# ft2232h-breakout-with-ground-planesch.net
KiCad netlist of a schematic drawn in EAGLE
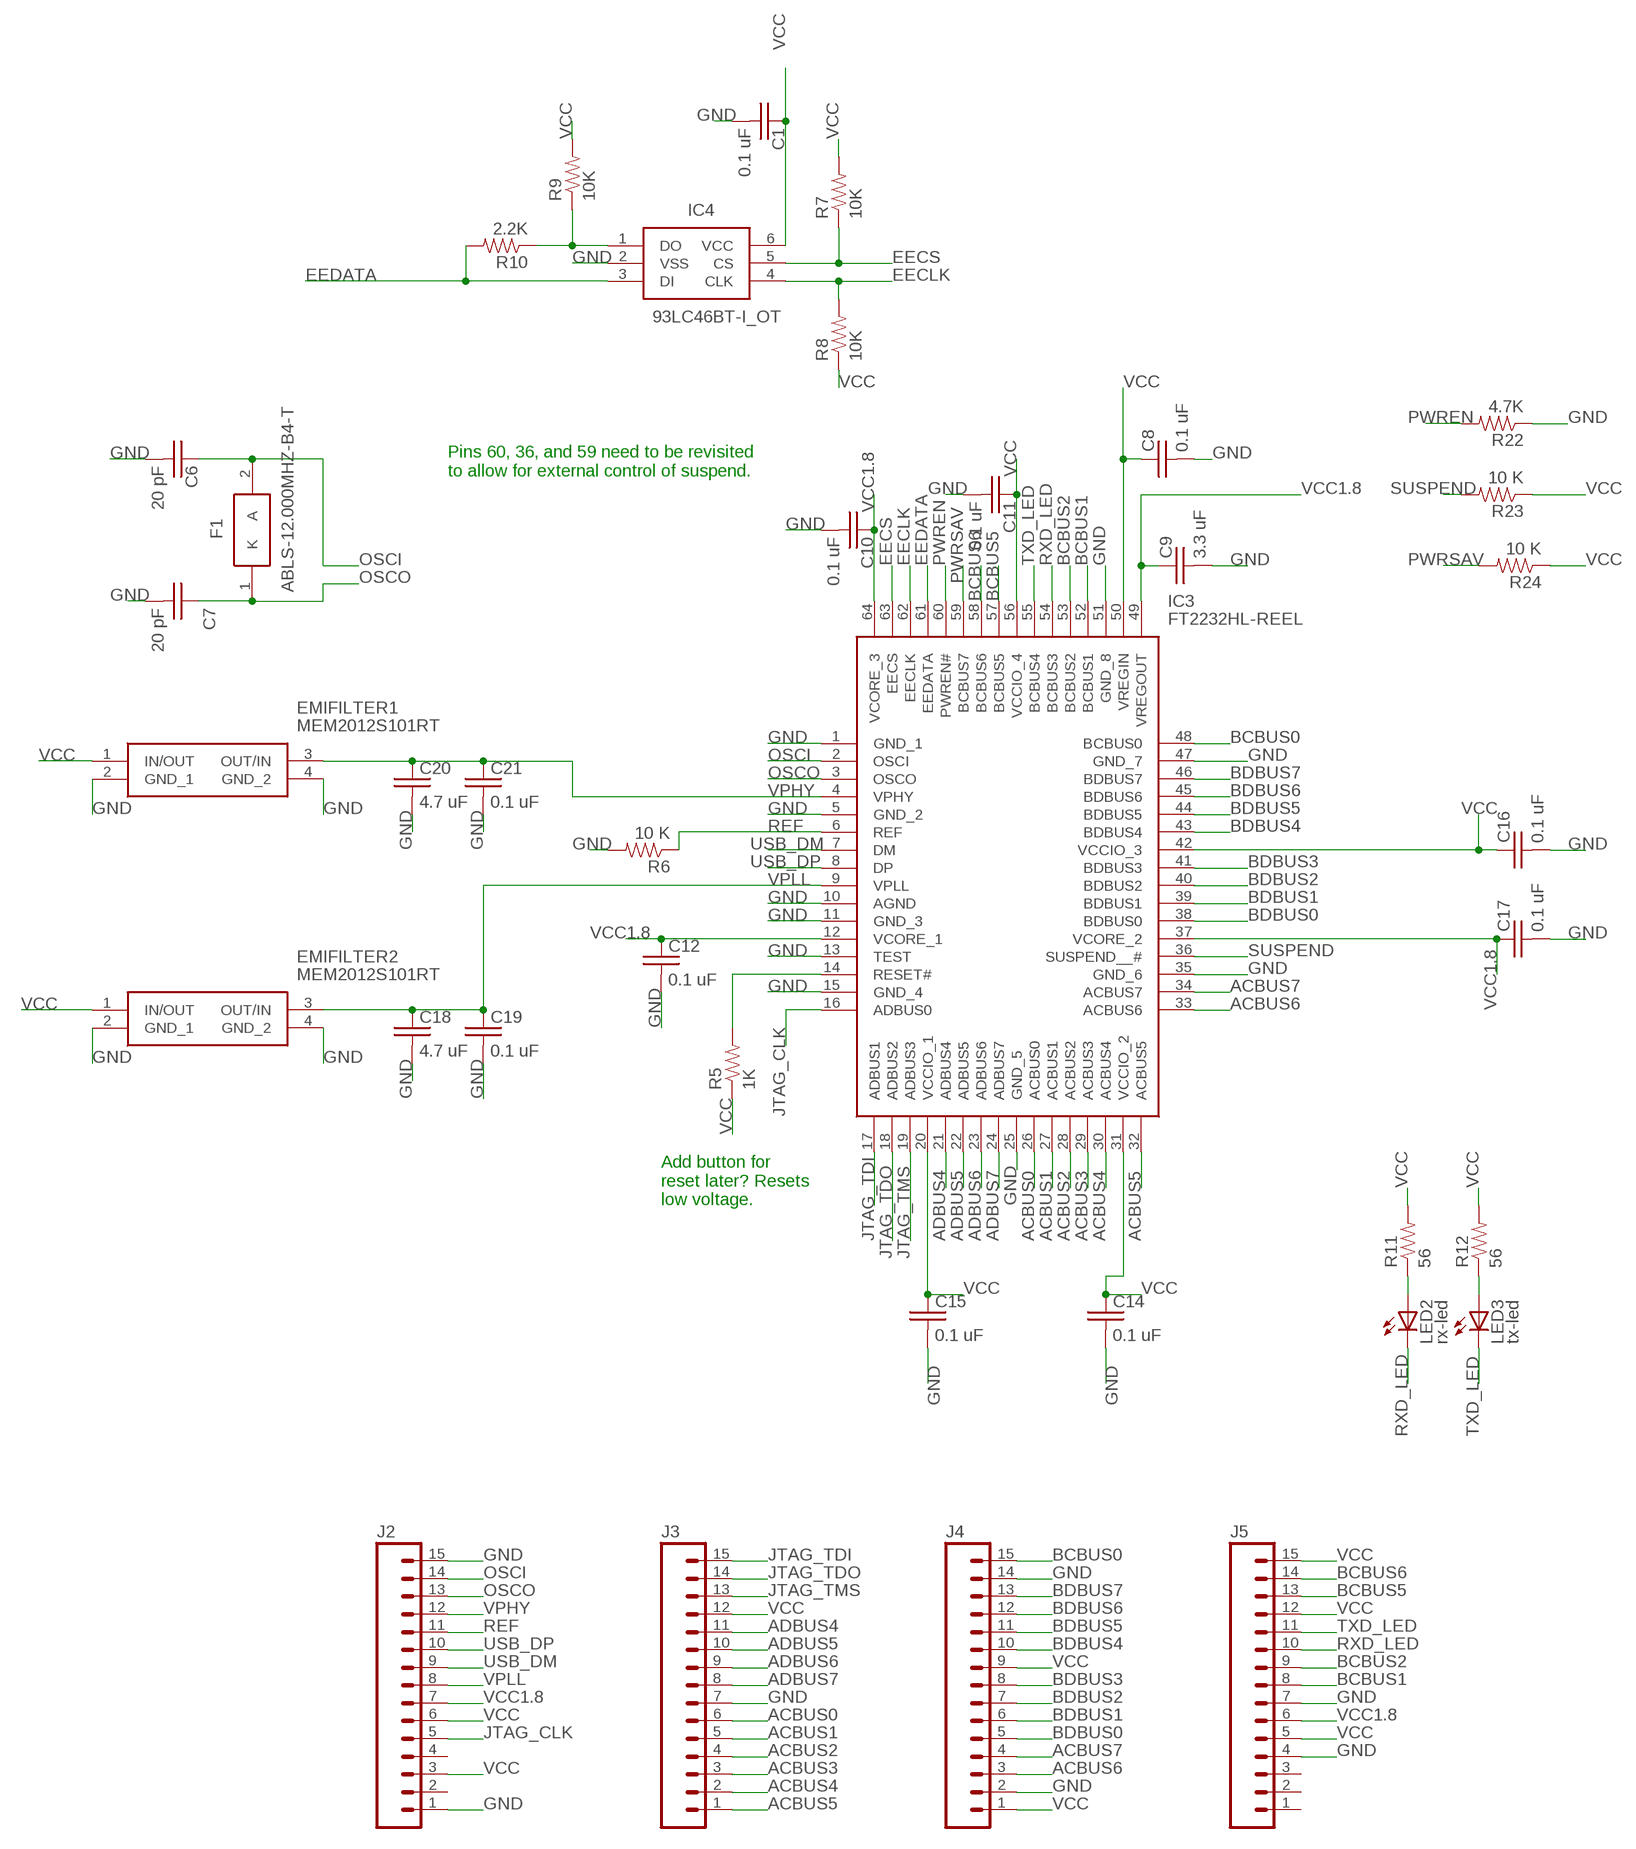
[diagram p0: schematic, sheet 1]
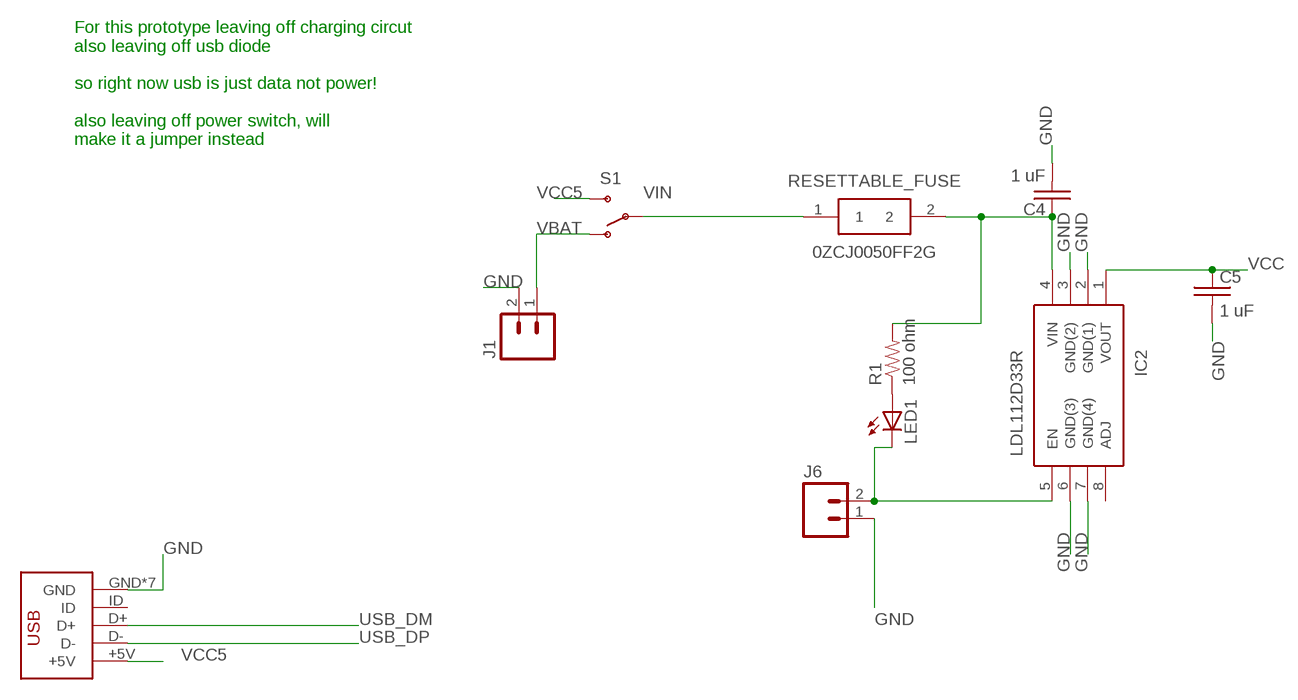
[diagram p1: schematic, sheet 2]

(export (version "E")
  (design (tool "Eeschema 10.0.6"))
  (components
    (comp (ref "C1")
      (value "0.1 uF")
      (footprint "eagle-import:C0805")
      (libsource (lib "eagle-import") (part "C-USC0805"))
    )
    (comp (ref "C6")
      (value "20 pF")
      (footprint "eagle-import:C0805")
      (libsource (lib "eagle-import") (part "C-USC0805"))
    )
    (comp (ref "C7")
      (value "20 pF")
      (footprint "eagle-import:C0805")
      (libsource (lib "eagle-import") (part "C-USC0805"))
    )
    (comp (ref "C8")
      (value "0.1 uF")
      (footprint "eagle-import:C0805")
      (libsource (lib "eagle-import") (part "C-USC0805"))
    )
    (comp (ref "C9")
      (value "3.3 uF")
      (footprint "eagle-import:C0805")
      (libsource (lib "eagle-import") (part "C-USC0805"))
    )
    (comp (ref "C10")
      (value "0.1 uF")
      (footprint "eagle-import:C0805")
      (libsource (lib "eagle-import") (part "C-USC0805"))
    )
    (comp (ref "C11")
      (value "0.1 uF")
      (footprint "eagle-import:C0805")
      (libsource (lib "eagle-import") (part "C-USC0805"))
    )
    (comp (ref "C12")
      (value "0.1 uF")
      (footprint "eagle-import:C0805")
      (libsource (lib "eagle-import") (part "C-USC0805"))
    )
    (comp (ref "C14")
      (value "0.1 uF")
      (footprint "eagle-import:C0805")
      (libsource (lib "eagle-import") (part "C-USC0805"))
    )
    (comp (ref "C15")
      (value "0.1 uF")
      (footprint "eagle-import:C0805")
      (libsource (lib "eagle-import") (part "C-USC0805"))
    )
    (comp (ref "C16")
      (value "0.1 uF")
      (footprint "eagle-import:C0805")
      (libsource (lib "eagle-import") (part "C-USC0805"))
    )
    (comp (ref "C17")
      (value "0.1 uF")
      (footprint "eagle-import:C0805")
      (libsource (lib "eagle-import") (part "C-USC0805"))
    )
    (comp (ref "C18")
      (value "4.7 uF")
      (footprint "eagle-import:C0805")
      (libsource (lib "eagle-import") (part "C-USC0805"))
    )
    (comp (ref "C19")
      (value "0.1 uF")
      (footprint "eagle-import:C0805")
      (libsource (lib "eagle-import") (part "C-USC0805"))
    )
    (comp (ref "C20")
      (value "4.7 uF")
      (footprint "eagle-import:C0805")
      (libsource (lib "eagle-import") (part "C-USC0805"))
    )
    (comp (ref "C21")
      (value "0.1 uF")
      (footprint "eagle-import:C0805")
      (libsource (lib "eagle-import") (part "C-USC0805"))
    )
    (comp (ref "EMIFILTER1")
      (value "MEM2012S101RT")
      (footprint "eagle-import:MEM2012S101RT")
      (libsource (lib "eagle-import") (part "MEM2012S101RT"))
    )
    (comp (ref "EMIFILTER2")
      (value "MEM2012S101RT")
      (footprint "eagle-import:MEM2012S101RT")
      (libsource (lib "eagle-import") (part "MEM2012S101RT"))
    )
    (comp (ref "F1")
      (value "ABLS-12.000MHZ-B4-T")
      (footprint "eagle-import:HC_49US-(AT49)_1")
      (fields
        (field (name "MOUSER_PART_NUMBER") "815-ABLS-12.0M-T")
        (field (name "RS_PART_NUMBER") "1710207")
      )
      (libsource (lib "eagle-import") (part "ABLS-12.000MHZ-B4-T"))
    )
    (comp (ref "IC3")
      (value "FT2232HL-REEL")
      (footprint "eagle-import:QFP50P1200X1200X160-64N")
      (fields (field (name "MOUSER_PART_NUMBER") "895-FT2232HL"))
      (libsource (lib "eagle-import") (part "FT2232HL-REEL"))
    )
    (comp (ref "IC4")
      (value "93LC46BT-I_OT")
      (footprint "eagle-import:SOT95P270X145-6N")
      (fields
        (field (name "MANUFACTURER_PART_NUMBER") "93LC46BT-I/OT")
        (field (name "MOUSER_PART_NUMBER") "579-93LC46BT-I/OT")
      )
      (libsource (lib "eagle-import") (part "93LC46BT-I_OT"))
    )
    (comp (ref "J2")
      (value "M15")
      (footprint "eagle-import:1X15")
      (libsource (lib "eagle-import") (part "M15"))
    )
    (comp (ref "J3")
      (value "M15")
      (footprint "eagle-import:1X15")
      (libsource (lib "eagle-import") (part "M15"))
    )
    (comp (ref "J4")
      (value "M15")
      (footprint "eagle-import:1X15")
      (libsource (lib "eagle-import") (part "M15"))
    )
    (comp (ref "J5")
      (value "M15")
      (footprint "eagle-import:1X15")
      (libsource (lib "eagle-import") (part "M15"))
    )
    (comp (ref "LED2")
      (value "rx-led")
      (footprint "eagle-import:LED3MM")
      (libsource (lib "eagle-import") (part "LED3MM"))
    )
    (comp (ref "LED3")
      (value "tx-led")
      (footprint "eagle-import:LED3MM")
      (libsource (lib "eagle-import") (part "LED3MM"))
    )
    (comp (ref "R5")
      (value "1K")
      (footprint "eagle-import:0805")
      (libsource (lib "eagle-import") (part "RESISTOR0805-RES"))
    )
    (comp (ref "R6")
      (value "10 K")
      (footprint "eagle-import:0805")
      (libsource (lib "eagle-import") (part "RESISTOR0805-RES"))
    )
    (comp (ref "R7")
      (value "10K")
      (footprint "eagle-import:0805")
      (libsource (lib "eagle-import") (part "RESISTOR0805-RES"))
    )
    (comp (ref "R8")
      (value "10K")
      (footprint "eagle-import:0805")
      (libsource (lib "eagle-import") (part "RESISTOR0805-RES"))
    )
    (comp (ref "R9")
      (value "10K")
      (footprint "eagle-import:0805")
      (libsource (lib "eagle-import") (part "RESISTOR0805-RES"))
    )
    (comp (ref "R10")
      (value "2.2K")
      (footprint "eagle-import:0805")
      (libsource (lib "eagle-import") (part "RESISTOR0805-RES"))
    )
    (comp (ref "R11")
      (value "56")
      (footprint "eagle-import:0805")
      (libsource (lib "eagle-import") (part "RESISTOR0805-RES"))
    )
    (comp (ref "R12")
      (value "56")
      (footprint "eagle-import:0805")
      (libsource (lib "eagle-import") (part "RESISTOR0805-RES"))
    )
    (comp (ref "R22")
      (value "4.7K")
      (footprint "eagle-import:0805")
      (libsource (lib "eagle-import") (part "RESISTOR0805-RES"))
    )
    (comp (ref "R23")
      (value "10 K")
      (footprint "eagle-import:0805")
      (libsource (lib "eagle-import") (part "RESISTOR0805-RES"))
    )
    (comp (ref "R24")
      (value "10 K")
      (footprint "eagle-import:0805")
      (libsource (lib "eagle-import") (part "RESISTOR0805-RES"))
    )
    (comp (ref "C4")
      (value "1 uF")
      (footprint "eagle-import:C0805")
      (libsource (lib "eagle-import") (part "C-USC0805"))
    )
    (comp (ref "C5")
      (value "1 uF")
      (footprint "eagle-import:C0805")
      (libsource (lib "eagle-import") (part "C-USC0805"))
    )
    (comp (ref "IC2")
      (value "LDL112D33R")
      (footprint "eagle-import:SOIC127P600X175-8N")
      (libsource (lib "eagle-import") (part "LDL112D33R"))
    )
    (comp (ref "J1")
      (value "M02PTH")
      (footprint "eagle-import:1X02")
      (libsource (lib "eagle-import") (part "M02PTH"))
    )
    (comp (ref "J6")
      (value "M02PTH")
      (footprint "eagle-import:1X02")
      (libsource (lib "eagle-import") (part "M02PTH"))
    )
    (comp (ref "LED1")
      (value "LED3MM")
      (footprint "eagle-import:LED3MM")
      (libsource (lib "eagle-import") (part "LED3MM"))
    )
    (comp (ref "R1")
      (value "100 ohm")
      (footprint "eagle-import:AXIAL-0.3-KIT")
      (libsource (lib "eagle-import") (part "RESISTORKIT"))
    )
    (comp (ref "RESETTABLE_FUSE")
      (value "0ZCJ0050FF2G")
      (footprint "eagle-import:FUSC3216X55N")
      (libsource (lib "eagle-import") (part "0ZCJ0050FF2G"))
    )
    (comp (ref "S1")
      (value "SWITCH-SPSTPTH")
      (footprint "eagle-import:SWITCH-SPDT")
      (libsource (lib "eagle-import") (part "SWITCH-SPSTPTH"))
    )
    (comp (ref "U$2")
      (value "DX4R005JJ2DX4R005JJ2")
      (footprint "eagle-import:DX4R005JJ2")
      (libsource (lib "eagle-import") (part "DX4R005JJ2DX4R005JJ2"))
    )
  )
  (nets
    (net (code "1") (name "ACBUS0") (class "Default")
      (node (ref "IC3") (pin "26") (pinfunction "ACBUS0_26") (pintype "bidirectional"))
      (node (ref "J3") (pin "6") (pinfunction "6_6") (pintype "passive"))
    )
    (net (code "2") (name "ACBUS1") (class "Default")
      (node (ref "IC3") (pin "27") (pinfunction "ACBUS1_27") (pintype "bidirectional"))
      (node (ref "J3") (pin "5") (pinfunction "5_5") (pintype "passive"))
    )
    (net (code "3") (name "ACBUS2") (class "Default")
      (node (ref "IC3") (pin "28") (pinfunction "ACBUS2_28") (pintype "bidirectional"))
      (node (ref "J3") (pin "4") (pinfunction "4_4") (pintype "passive"))
    )
    (net (code "4") (name "ACBUS3") (class "Default")
      (node (ref "IC3") (pin "29") (pinfunction "ACBUS3_29") (pintype "bidirectional"))
      (node (ref "J3") (pin "3") (pinfunction "3_3") (pintype "passive"))
    )
    (net (code "5") (name "ACBUS4") (class "Default")
      (node (ref "IC3") (pin "30") (pinfunction "ACBUS4_30") (pintype "bidirectional"))
      (node (ref "J3") (pin "2") (pinfunction "2_2") (pintype "passive"))
    )
    (net (code "6") (name "ACBUS5") (class "Default")
      (node (ref "IC3") (pin "32") (pinfunction "ACBUS5_32") (pintype "bidirectional"))
      (node (ref "J3") (pin "1") (pinfunction "1_1") (pintype "passive"))
    )
    (net (code "7") (name "ACBUS6") (class "Default")
      (node (ref "IC3") (pin "33") (pinfunction "ACBUS6_33") (pintype "bidirectional"))
      (node (ref "J4") (pin "3") (pinfunction "3_3") (pintype "passive"))
    )
    (net (code "8") (name "ACBUS7") (class "Default")
      (node (ref "IC3") (pin "34") (pinfunction "ACBUS7_34") (pintype "bidirectional"))
      (node (ref "J4") (pin "4") (pinfunction "4_4") (pintype "passive"))
    )
    (net (code "9") (name "ADBUS4") (class "Default")
      (node (ref "IC3") (pin "21") (pinfunction "ADBUS4_21") (pintype "bidirectional"))
      (node (ref "J3") (pin "11") (pinfunction "11_11") (pintype "passive"))
    )
    (net (code "10") (name "ADBUS5") (class "Default")
      (node (ref "IC3") (pin "22") (pinfunction "ADBUS5_22") (pintype "bidirectional"))
      (node (ref "J3") (pin "10") (pinfunction "10_10") (pintype "passive"))
    )
    (net (code "11") (name "ADBUS6") (class "Default")
      (node (ref "IC3") (pin "23") (pinfunction "ADBUS6_23") (pintype "bidirectional"))
      (node (ref "J3") (pin "9") (pinfunction "9_9") (pintype "passive"))
    )
    (net (code "12") (name "ADBUS7") (class "Default")
      (node (ref "IC3") (pin "24") (pinfunction "ADBUS7_24") (pintype "bidirectional"))
      (node (ref "J3") (pin "8") (pinfunction "8_8") (pintype "passive"))
    )
    (net (code "13") (name "BCBUS0") (class "Default")
      (node (ref "IC3") (pin "48") (pinfunction "BCBUS0_48") (pintype "bidirectional"))
      (node (ref "J4") (pin "15") (pinfunction "15_15") (pintype "passive"))
    )
    (net (code "14") (name "BCBUS1") (class "Default")
      (node (ref "IC3") (pin "52") (pinfunction "BCBUS1_52") (pintype "bidirectional"))
      (node (ref "J5") (pin "8") (pinfunction "8_8") (pintype "passive"))
    )
    (net (code "15") (name "BCBUS2") (class "Default")
      (node (ref "IC3") (pin "53") (pinfunction "BCBUS2_53") (pintype "bidirectional"))
      (node (ref "J5") (pin "9") (pinfunction "9_9") (pintype "passive"))
    )
    (net (code "16") (name "BCBUS5") (class "Default")
      (node (ref "IC3") (pin "57") (pinfunction "BCBUS5_57") (pintype "bidirectional"))
      (node (ref "J5") (pin "13") (pinfunction "13_13") (pintype "passive"))
    )
    (net (code "17") (name "BCBUS6") (class "Default")
      (node (ref "IC3") (pin "58") (pinfunction "BCBUS6_58") (pintype "bidirectional"))
      (node (ref "J5") (pin "14") (pinfunction "14_14") (pintype "passive"))
    )
    (net (code "18") (name "BDBUS0") (class "Default")
      (node (ref "IC3") (pin "38") (pinfunction "BDBUS0_38") (pintype "bidirectional"))
      (node (ref "J4") (pin "5") (pinfunction "5_5") (pintype "passive"))
    )
    (net (code "19") (name "BDBUS1") (class "Default")
      (node (ref "IC3") (pin "39") (pinfunction "BDBUS1_39") (pintype "bidirectional"))
      (node (ref "J4") (pin "6") (pinfunction "6_6") (pintype "passive"))
    )
    (net (code "20") (name "BDBUS2") (class "Default")
      (node (ref "IC3") (pin "40") (pinfunction "BDBUS2_40") (pintype "bidirectional"))
      (node (ref "J4") (pin "7") (pinfunction "7_7") (pintype "passive"))
    )
    (net (code "21") (name "BDBUS3") (class "Default")
      (node (ref "IC3") (pin "41") (pinfunction "BDBUS3_41") (pintype "bidirectional"))
      (node (ref "J4") (pin "8") (pinfunction "8_8") (pintype "passive"))
    )
    (net (code "22") (name "BDBUS4") (class "Default")
      (node (ref "IC3") (pin "43") (pinfunction "BDBUS4_43") (pintype "bidirectional"))
      (node (ref "J4") (pin "10") (pinfunction "10_10") (pintype "passive"))
    )
    (net (code "23") (name "BDBUS5") (class "Default")
      (node (ref "IC3") (pin "44") (pinfunction "BDBUS5_44") (pintype "bidirectional"))
      (node (ref "J4") (pin "11") (pinfunction "11_11") (pintype "passive"))
    )
    (net (code "24") (name "BDBUS6") (class "Default")
      (node (ref "IC3") (pin "45") (pinfunction "BDBUS6_45") (pintype "bidirectional"))
      (node (ref "J4") (pin "12") (pinfunction "12_12") (pintype "passive"))
    )
    (net (code "25") (name "BDBUS7") (class "Default")
      (node (ref "IC3") (pin "46") (pinfunction "BDBUS7_46") (pintype "bidirectional"))
      (node (ref "J4") (pin "13") (pinfunction "13_13") (pintype "passive"))
    )
    (net (code "26") (name "EECLK") (class "Default")
      (node (ref "IC3") (pin "62") (pinfunction "EECLK_62") (pintype "bidirectional"))
      (node (ref "IC4") (pin "4") (pinfunction "CLK_4") (pintype "input"))
      (node (ref "R8") (pin "2") (pinfunction "2_2") (pintype "passive"))
    )
    (net (code "27") (name "EECS") (class "Default")
      (node (ref "IC3") (pin "63") (pinfunction "EECS_63") (pintype "bidirectional"))
      (node (ref "IC4") (pin "5") (pinfunction "CS_5") (pintype "input"))
      (node (ref "R7") (pin "1") (pinfunction "1_1") (pintype "passive"))
    )
    (net (code "28") (name "EEDATA") (class "Default")
      (node (ref "IC3") (pin "61") (pinfunction "EEDATA_61") (pintype "bidirectional"))
      (node (ref "IC4") (pin "3") (pinfunction "DI_3") (pintype "bidirectional"))
      (node (ref "R10") (pin "2") (pinfunction "2_2") (pintype "passive"))
    )
    (net (code "29") (name "GND") (class "Default")
      (node (ref "C1") (pin "2") (pinfunction "2_2") (pintype "passive"))
      (node (ref "C10") (pin "2") (pinfunction "2_2") (pintype "passive"))
      (node (ref "C11") (pin "2") (pinfunction "2_2") (pintype "passive"))
      (node (ref "C12") (pin "2") (pinfunction "2_2") (pintype "passive"))
      (node (ref "C14") (pin "2") (pinfunction "2_2") (pintype "passive"))
      (node (ref "C15") (pin "2") (pinfunction "2_2") (pintype "passive"))
      (node (ref "C16") (pin "2") (pinfunction "2_2") (pintype "passive"))
      (node (ref "C17") (pin "2") (pinfunction "2_2") (pintype "passive"))
      (node (ref "C18") (pin "2") (pinfunction "2_2") (pintype "passive"))
      (node (ref "C19") (pin "2") (pinfunction "2_2") (pintype "passive"))
      (node (ref "C20") (pin "2") (pinfunction "2_2") (pintype "passive"))
      (node (ref "C21") (pin "2") (pinfunction "2_2") (pintype "passive"))
      (node (ref "C4") (pin "2") (pinfunction "2_2") (pintype "passive"))
      (node (ref "C5") (pin "2") (pinfunction "2_2") (pintype "passive"))
      (node (ref "C6") (pin "2") (pinfunction "2_2") (pintype "passive"))
      (node (ref "C7") (pin "2") (pinfunction "2_2") (pintype "passive"))
      (node (ref "C8") (pin "2") (pinfunction "2_2") (pintype "passive"))
      (node (ref "C9") (pin "2") (pinfunction "2_2") (pintype "passive"))
      (node (ref "EMIFILTER1") (pin "2") (pinfunction "GND_1_2") (pintype "bidirectional"))
      (node (ref "EMIFILTER1") (pin "4") (pinfunction "GND_2_4") (pintype "bidirectional"))
      (node (ref "EMIFILTER2") (pin "2") (pinfunction "GND_1_2") (pintype "bidirectional"))
      (node (ref "EMIFILTER2") (pin "4") (pinfunction "GND_2_4") (pintype "bidirectional"))
      (node (ref "IC2") (pin "2") (pinfunction "GND(1)_2") (pintype "bidirectional"))
      (node (ref "IC2") (pin "3") (pinfunction "GND(2)_3") (pintype "bidirectional"))
      (node (ref "IC2") (pin "6") (pinfunction "GND(3)_6") (pintype "bidirectional"))
      (node (ref "IC2") (pin "7") (pinfunction "GND(4)_7") (pintype "bidirectional"))
      (node (ref "IC3") (pin "1") (pinfunction "GND_1_1") (pintype "bidirectional"))
      (node (ref "IC3") (pin "10") (pinfunction "AGND_10") (pintype "bidirectional"))
      (node (ref "IC3") (pin "11") (pinfunction "GND_3_11") (pintype "bidirectional"))
      (node (ref "IC3") (pin "13") (pinfunction "TEST_13") (pintype "bidirectional"))
      (node (ref "IC3") (pin "15") (pinfunction "GND_4_15") (pintype "bidirectional"))
      (node (ref "IC3") (pin "25") (pinfunction "GND_5_25") (pintype "bidirectional"))
      (node (ref "IC3") (pin "35") (pinfunction "GND_6_35") (pintype "bidirectional"))
      (node (ref "IC3") (pin "47") (pinfunction "GND_7_47") (pintype "bidirectional"))
      (node (ref "IC3") (pin "5") (pinfunction "GND_2_5") (pintype "bidirectional"))
      (node (ref "IC3") (pin "51") (pinfunction "GND_8_51") (pintype "bidirectional"))
      (node (ref "IC4") (pin "2") (pinfunction "VSS_2") (pintype "power_in"))
      (node (ref "J1") (pin "2") (pinfunction "2_2") (pintype "passive"))
      (node (ref "J2") (pin "1") (pinfunction "1_1") (pintype "passive"))
      (node (ref "J2") (pin "15") (pinfunction "15_15") (pintype "passive"))
      (node (ref "J3") (pin "7") (pinfunction "7_7") (pintype "passive"))
      (node (ref "J4") (pin "14") (pinfunction "14_14") (pintype "passive"))
      (node (ref "J4") (pin "2") (pinfunction "2_2") (pintype "passive"))
      (node (ref "J5") (pin "4") (pinfunction "4_4") (pintype "passive"))
      (node (ref "J5") (pin "7") (pinfunction "7_7") (pintype "passive"))
      (node (ref "J6") (pin "1") (pinfunction "1_1") (pintype "passive"))
      (node (ref "R22") (pin "1") (pinfunction "1_1") (pintype "passive"))
      (node (ref "R6") (pin "2") (pinfunction "2_2") (pintype "passive"))
      (node (ref "U$2") (pin "GND") (pinfunction "GND_GND") (pintype "bidirectional"))
      (node (ref "U$2") (pin "P$10") (pinfunction "GND_P$10") (pintype "bidirectional"))
      (node (ref "U$2") (pin "P$11") (pinfunction "GND_P$11") (pintype "bidirectional"))
      (node (ref "U$2") (pin "P$6") (pinfunction "GND_P$6") (pintype "bidirectional"))
      (node (ref "U$2") (pin "P$7") (pinfunction "GND_P$7") (pintype "bidirectional"))
      (node (ref "U$2") (pin "P$8") (pinfunction "GND_P$8") (pintype "bidirectional"))
      (node (ref "U$2") (pin "P$9") (pinfunction "GND_P$9") (pintype "bidirectional"))
    )
    (net (code "30") (name "JTAG_CLK") (class "Default")
      (node (ref "IC3") (pin "16") (pinfunction "ADBUS0_16") (pintype "bidirectional"))
      (node (ref "J2") (pin "5") (pinfunction "5_5") (pintype "passive"))
    )
    (net (code "31") (name "JTAG_TDI") (class "Default")
      (node (ref "IC3") (pin "17") (pinfunction "ADBUS1_17") (pintype "bidirectional"))
      (node (ref "J3") (pin "15") (pinfunction "15_15") (pintype "passive"))
    )
    (net (code "32") (name "JTAG_TDO") (class "Default")
      (node (ref "IC3") (pin "18") (pinfunction "ADBUS2_18") (pintype "bidirectional"))
      (node (ref "J3") (pin "14") (pinfunction "14_14") (pintype "passive"))
    )
    (net (code "33") (name "JTAG_TMS") (class "Default")
      (node (ref "IC3") (pin "19") (pinfunction "ADBUS3_19") (pintype "bidirectional"))
      (node (ref "J3") (pin "13") (pinfunction "13_13") (pintype "passive"))
    )
    (net (code "34") (name "Net-(IC2-EN)") (class "Default")
      (node (ref "IC2") (pin "5") (pinfunction "EN_5") (pintype "bidirectional"))
      (node (ref "J6") (pin "2") (pinfunction "2_2") (pintype "passive"))
      (node (ref "LED1") (pin "K") (pinfunction "C_K") (pintype "output"))
    )
    (net (code "35") (name "Net-(IC2-VIN)") (class "Default")
      (node (ref "C4") (pin "1") (pinfunction "1_1") (pintype "passive"))
      (node (ref "IC2") (pin "4") (pinfunction "VIN_4") (pintype "bidirectional"))
      (node (ref "R1") (pin "P$2") (pinfunction "2_P$2") (pintype "passive"))
      (node (ref "RESETTABLE_FUSE") (pin "2") (pinfunction "2_2") (pintype "passive"))
    )
    (net (code "36") (name "Net-(IC3-RESET#)") (class "Default")
      (node (ref "IC3") (pin "14") (pinfunction "RESET#_14") (pintype "bidirectional"))
      (node (ref "R5") (pin "2") (pinfunction "2_2") (pintype "passive"))
    )
    (net (code "37") (name "Net-(IC4-DO)") (class "Default")
      (node (ref "IC4") (pin "1") (pinfunction "DO_1") (pintype "bidirectional"))
      (node (ref "R10") (pin "1") (pinfunction "1_1") (pintype "passive"))
      (node (ref "R9") (pin "1") (pinfunction "1_1") (pintype "passive"))
    )
    (net (code "38") (name "Net-(LED2-PadA)") (class "Default")
      (node (ref "LED2") (pin "A") (pinfunction "A_A") (pintype "input"))
      (node (ref "R11") (pin "1") (pinfunction "1_1") (pintype "passive"))
    )
    (net (code "39") (name "Net-(LED3-PadA)") (class "Default")
      (node (ref "LED3") (pin "A") (pinfunction "A_A") (pintype "input"))
      (node (ref "R12") (pin "1") (pinfunction "1_1") (pintype "passive"))
    )
    (net (code "40") (name "Net-(R1-1)") (class "Default")
      (node (ref "LED1") (pin "A") (pinfunction "A_A") (pintype "input"))
      (node (ref "R1") (pin "P$1") (pinfunction "1_P$1") (pintype "passive"))
    )
    (net (code "41") (name "OSCI") (class "Default")
      (node (ref "C6") (pin "1") (pinfunction "1_1") (pintype "passive"))
      (node (ref "F1") (pin "2") (pinfunction "A_2") (pintype "bidirectional"))
      (node (ref "IC3") (pin "2") (pinfunction "OSCI_2") (pintype "bidirectional"))
      (node (ref "J2") (pin "14") (pinfunction "14_14") (pintype "passive"))
    )
    (net (code "42") (name "OSCO") (class "Default")
      (node (ref "C7") (pin "1") (pinfunction "1_1") (pintype "passive"))
      (node (ref "F1") (pin "1") (pinfunction "K_1") (pintype "bidirectional"))
      (node (ref "IC3") (pin "3") (pinfunction "OSCO_3") (pintype "bidirectional"))
      (node (ref "J2") (pin "13") (pinfunction "13_13") (pintype "passive"))
    )
    (net (code "43") (name "PWREN") (class "Default")
      (node (ref "IC3") (pin "60") (pinfunction "PWREN#_60") (pintype "bidirectional"))
      (node (ref "R22") (pin "2") (pinfunction "2_2") (pintype "passive"))
    )
    (net (code "44") (name "PWRSAV") (class "Default")
      (node (ref "IC3") (pin "59") (pinfunction "BCBUS7_59") (pintype "bidirectional"))
      (node (ref "R24") (pin "2") (pinfunction "2_2") (pintype "passive"))
    )
    (net (code "45") (name "REF") (class "Default")
      (node (ref "IC3") (pin "6") (pinfunction "REF_6") (pintype "bidirectional"))
      (node (ref "J2") (pin "11") (pinfunction "11_11") (pintype "passive"))
      (node (ref "R6") (pin "1") (pinfunction "1_1") (pintype "passive"))
    )
    (net (code "46") (name "RXD_LED") (class "Default")
      (node (ref "IC3") (pin "54") (pinfunction "BCBUS3_54") (pintype "bidirectional"))
      (node (ref "J5") (pin "10") (pinfunction "10_10") (pintype "passive"))
      (node (ref "LED2") (pin "K") (pinfunction "C_K") (pintype "output"))
    )
    (net (code "47") (name "SUSPEND") (class "Default")
      (node (ref "IC3") (pin "36") (pinfunction "SUSPEND__#_36") (pintype "bidirectional"))
      (node (ref "R23") (pin "2") (pinfunction "2_2") (pintype "passive"))
    )
    (net (code "48") (name "TXD_LED") (class "Default")
      (node (ref "IC3") (pin "55") (pinfunction "BCBUS4_55") (pintype "bidirectional"))
      (node (ref "J5") (pin "11") (pinfunction "11_11") (pintype "passive"))
      (node (ref "LED3") (pin "K") (pinfunction "C_K") (pintype "output"))
    )
    (net (code "49") (name "USB_DM") (class "Default")
      (node (ref "IC3") (pin "7") (pinfunction "DM_7") (pintype "bidirectional"))
      (node (ref "J2") (pin "9") (pinfunction "9_9") (pintype "passive"))
      (node (ref "U$2") (pin "D+") (pinfunction "D+_D+") (pintype "bidirectional"))
    )
    (net (code "50") (name "USB_DP") (class "Default")
      (node (ref "IC3") (pin "8") (pinfunction "DP_8") (pintype "bidirectional"))
      (node (ref "J2") (pin "10") (pinfunction "10_10") (pintype "passive"))
      (node (ref "U$2") (pin "D-") (pinfunction "D-_D-") (pintype "bidirectional"))
    )
    (net (code "51") (name "VBAT") (class "Default")
      (node (ref "J1") (pin "1") (pinfunction "1_1") (pintype "passive"))
      (node (ref "S1") (pin "1") (pinfunction "O_1") (pintype "passive"))
    )
    (net (code "52") (name "VCC") (class "Default")
      (node (ref "C1") (pin "1") (pinfunction "1_1") (pintype "passive"))
      (node (ref "C11") (pin "1") (pinfunction "1_1") (pintype "passive"))
      (node (ref "C14") (pin "1") (pinfunction "1_1") (pintype "passive"))
      (node (ref "C15") (pin "1") (pinfunction "1_1") (pintype "passive"))
      (node (ref "C16") (pin "1") (pinfunction "1_1") (pintype "passive"))
      (node (ref "C5") (pin "1") (pinfunction "1_1") (pintype "passive"))
      (node (ref "C8") (pin "1") (pinfunction "1_1") (pintype "passive"))
      (node (ref "EMIFILTER1") (pin "1") (pinfunction "IN/OUT_1") (pintype "bidirectional"))
      (node (ref "EMIFILTER2") (pin "1") (pinfunction "IN/OUT_1") (pintype "bidirectional"))
      (node (ref "IC2") (pin "1") (pinfunction "VOUT_1") (pintype "bidirectional"))
      (node (ref "IC3") (pin "20") (pinfunction "VCCIO_1_20") (pintype "bidirectional"))
      (node (ref "IC3") (pin "31") (pinfunction "VCCIO_2_31") (pintype "bidirectional"))
      (node (ref "IC3") (pin "42") (pinfunction "VCCIO_3_42") (pintype "bidirectional"))
      (node (ref "IC3") (pin "50") (pinfunction "VREGIN_50") (pintype "bidirectional"))
      (node (ref "IC3") (pin "56") (pinfunction "VCCIO_4_56") (pintype "bidirectional"))
      (node (ref "IC4") (pin "6") (pinfunction "VCC_6") (pintype "power_in"))
      (node (ref "J2") (pin "3") (pinfunction "3_3") (pintype "passive"))
      (node (ref "J2") (pin "6") (pinfunction "6_6") (pintype "passive"))
      (node (ref "J3") (pin "12") (pinfunction "12_12") (pintype "passive"))
      (node (ref "J4") (pin "1") (pinfunction "1_1") (pintype "passive"))
      (node (ref "J4") (pin "9") (pinfunction "9_9") (pintype "passive"))
      (node (ref "J5") (pin "12") (pinfunction "12_12") (pintype "passive"))
      (node (ref "J5") (pin "15") (pinfunction "15_15") (pintype "passive"))
      (node (ref "J5") (pin "5") (pinfunction "5_5") (pintype "passive"))
      (node (ref "R11") (pin "2") (pinfunction "2_2") (pintype "passive"))
      (node (ref "R12") (pin "2") (pinfunction "2_2") (pintype "passive"))
      (node (ref "R23") (pin "1") (pinfunction "1_1") (pintype "passive"))
      (node (ref "R24") (pin "1") (pinfunction "1_1") (pintype "passive"))
      (node (ref "R5") (pin "1") (pinfunction "1_1") (pintype "passive"))
      (node (ref "R7") (pin "2") (pinfunction "2_2") (pintype "passive"))
      (node (ref "R8") (pin "1") (pinfunction "1_1") (pintype "passive"))
      (node (ref "R9") (pin "2") (pinfunction "2_2") (pintype "passive"))
    )
    (net (code "53") (name "VCC1.8") (class "Default")
      (node (ref "C10") (pin "1") (pinfunction "1_1") (pintype "passive"))
      (node (ref "C12") (pin "1") (pinfunction "1_1") (pintype "passive"))
      (node (ref "C17") (pin "1") (pinfunction "1_1") (pintype "passive"))
      (node (ref "C9") (pin "1") (pinfunction "1_1") (pintype "passive"))
      (node (ref "IC3") (pin "12") (pinfunction "VCORE_1_12") (pintype "bidirectional"))
      (node (ref "IC3") (pin "37") (pinfunction "VCORE_2_37") (pintype "bidirectional"))
      (node (ref "IC3") (pin "49") (pinfunction "VREGOUT_49") (pintype "bidirectional"))
      (node (ref "IC3") (pin "64") (pinfunction "VCORE_3_64") (pintype "bidirectional"))
      (node (ref "J2") (pin "7") (pinfunction "7_7") (pintype "passive"))
      (node (ref "J5") (pin "6") (pinfunction "6_6") (pintype "passive"))
    )
    (net (code "54") (name "VCC5") (class "Default")
      (node (ref "S1") (pin "3") (pinfunction "S_3") (pintype "passive"))
      (node (ref "U$2") (pin "+5V") (pinfunction "+5V_+5V") (pintype "bidirectional"))
    )
    (net (code "55") (name "VIN") (class "Default")
      (node (ref "RESETTABLE_FUSE") (pin "1") (pinfunction "1_1") (pintype "passive"))
      (node (ref "S1") (pin "2") (pinfunction "P_2") (pintype "passive"))
    )
    (net (code "56") (name "VPHY") (class "Default")
      (node (ref "C20") (pin "1") (pinfunction "1_1") (pintype "passive"))
      (node (ref "C21") (pin "1") (pinfunction "1_1") (pintype "passive"))
      (node (ref "EMIFILTER1") (pin "3") (pinfunction "OUT/IN_3") (pintype "bidirectional"))
      (node (ref "IC3") (pin "4") (pinfunction "VPHY_4") (pintype "bidirectional"))
      (node (ref "J2") (pin "12") (pinfunction "12_12") (pintype "passive"))
    )
    (net (code "57") (name "VPLL") (class "Default")
      (node (ref "C18") (pin "1") (pinfunction "1_1") (pintype "passive"))
      (node (ref "C19") (pin "1") (pinfunction "1_1") (pintype "passive"))
      (node (ref "EMIFILTER2") (pin "3") (pinfunction "OUT/IN_3") (pintype "bidirectional"))
      (node (ref "IC3") (pin "9") (pinfunction "VPLL_9") (pintype "bidirectional"))
      (node (ref "J2") (pin "8") (pinfunction "8_8") (pintype "passive"))
    )
    (net (code "58") (name "unconnected-(IC2-ADJ-Pad8)") (class "Default")
      (node (ref "IC2") (pin "8") (pinfunction "ADJ_8") (pintype "bidirectional"))
    )
    (net (code "59") (name "unconnected-(J2-Pad2)") (class "Default")
      (node (ref "J2") (pin "2") (pinfunction "2_2") (pintype "passive"))
    )
    (net (code "60") (name "unconnected-(J2-Pad4)") (class "Default")
      (node (ref "J2") (pin "4") (pinfunction "4_4") (pintype "passive"))
    )
    (net (code "61") (name "unconnected-(J5-Pad1)") (class "Default")
      (node (ref "J5") (pin "1") (pinfunction "1_1") (pintype "passive"))
    )
    (net (code "62") (name "unconnected-(J5-Pad2)") (class "Default")
      (node (ref "J5") (pin "2") (pinfunction "2_2") (pintype "passive"))
    )
    (net (code "63") (name "unconnected-(J5-Pad3)") (class "Default")
      (node (ref "J5") (pin "3") (pinfunction "3_3") (pintype "passive"))
    )
    (net (code "64") (name "unconnected-(U$2-PadID)") (class "Default")
      (node (ref "U$2") (pin "ID") (pinfunction "ID_ID") (pintype "bidirectional"))
    )
  )
)
